# dc_motor_driver_v10.net
KiCad netlist of a schematic drawn in EAGLE
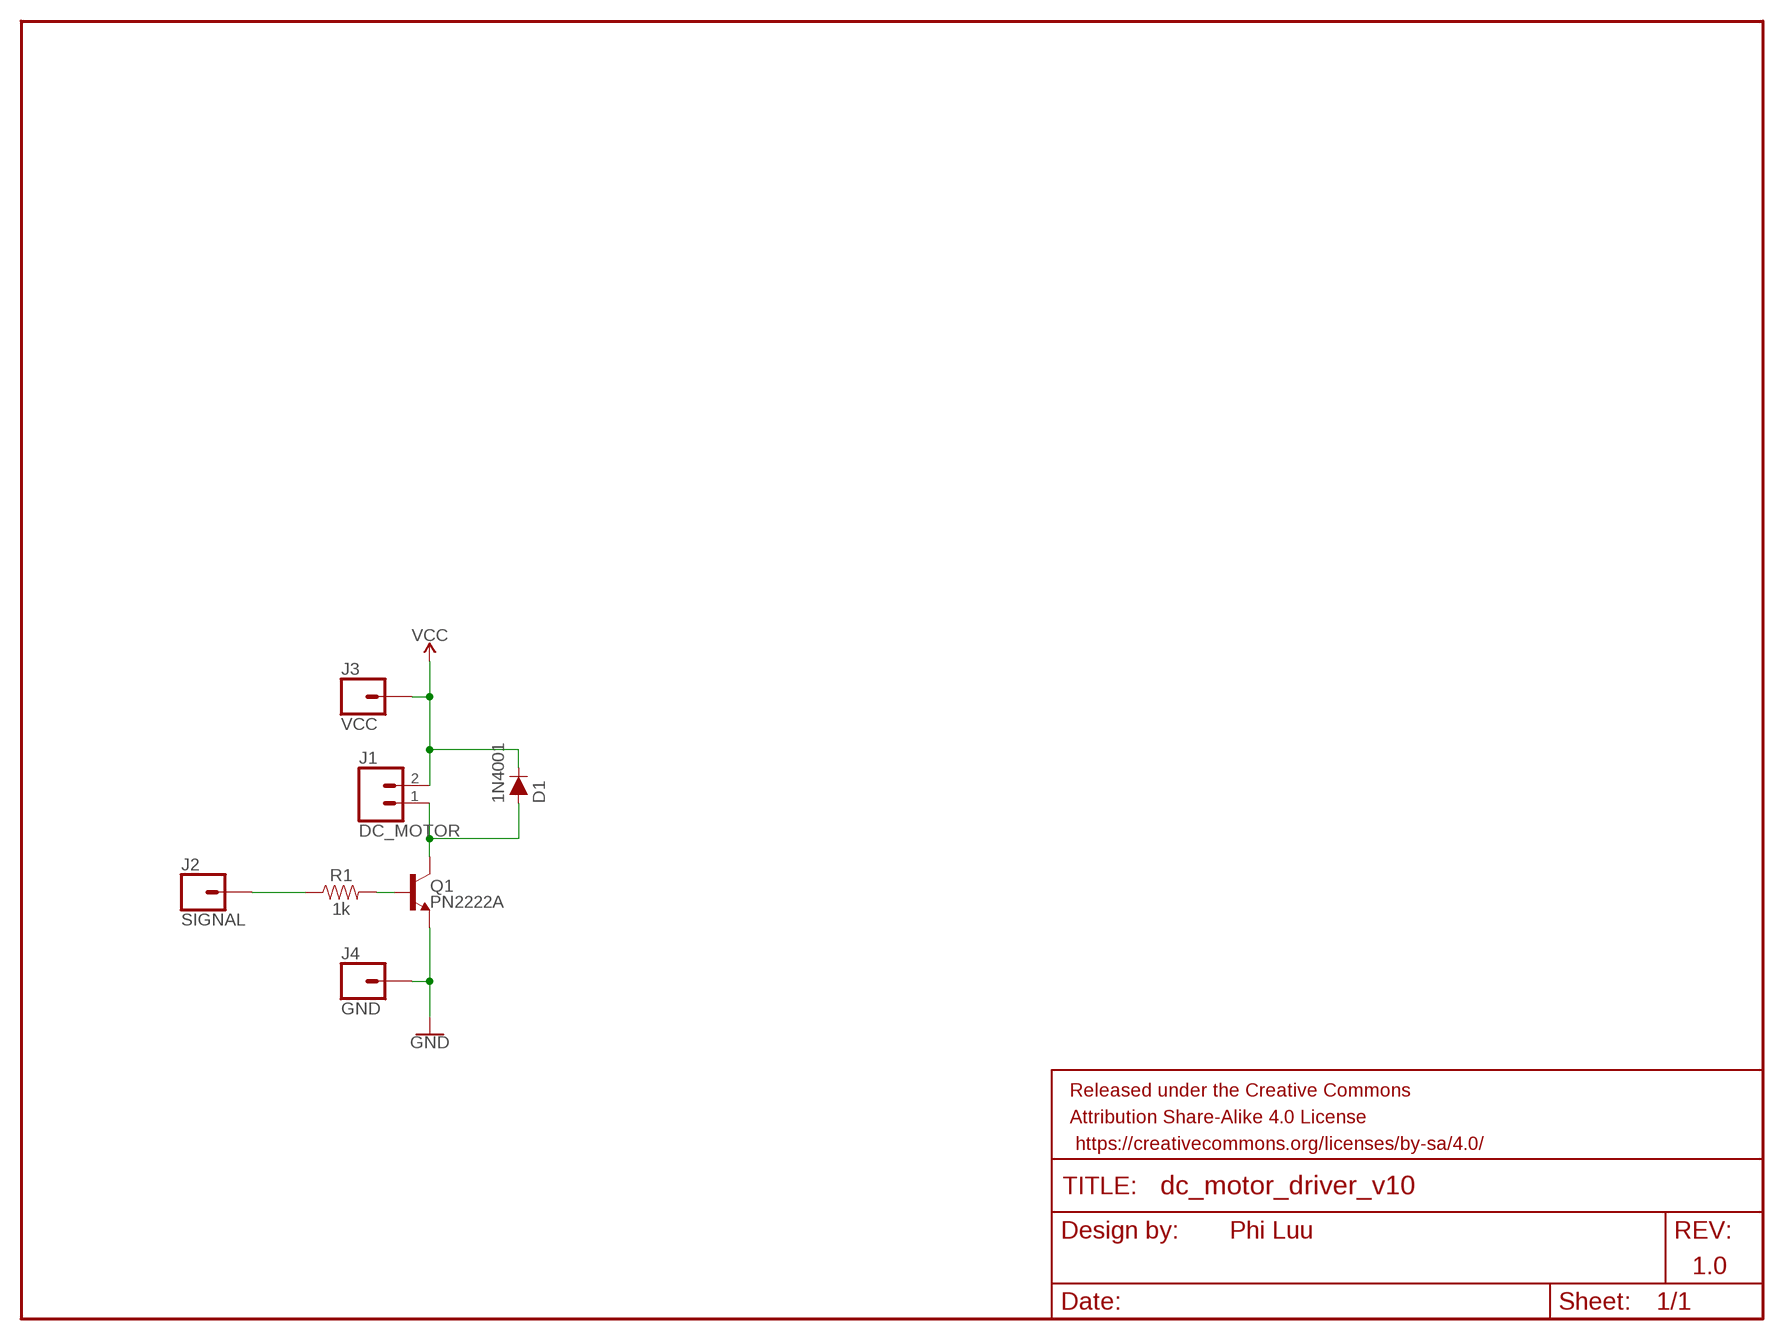
[diagram p0: schematic, sheet 1]

(export (version "E")
  (design (tool "Eeschema 10.0.6"))
  (components
    (comp (ref "D1")
      (value "1N4001")
      (footprint "eagle-import:DIODE-1N4001")
      (libsource (lib "eagle-import") (part "DIODE-PTH"))
    )
    (comp (ref "FRAME1")
      (value "FRAME-LETTER")
      (footprint "eagle-import:CREATIVE_COMMONS")
      (libsource (lib "eagle-import") (part "FRAME-LETTER"))
    )
    (comp (ref "J1")
      (value "DC_MOTOR")
      (footprint "eagle-import:1X02")
      (libsource (lib "eagle-import") (part "CONN_02"))
    )
    (comp (ref "J2")
      (value "SIGNAL")
      (footprint "eagle-import:1X01")
      (libsource (lib "eagle-import") (part "CONN_01"))
    )
    (comp (ref "J3")
      (value "VCC")
      (footprint "eagle-import:1X01")
      (libsource (lib "eagle-import") (part "CONN_01"))
    )
    (comp (ref "J4")
      (value "GND")
      (footprint "eagle-import:1X01")
      (libsource (lib "eagle-import") (part "CONN_01"))
    )
    (comp (ref "Q1")
      (value "PN2222A")
      (footprint "eagle-import:TO-92")
      (libsource (lib "eagle-import") (part "TRANS_NPN-P2N2222A"))
    )
    (comp (ref "R1")
      (value "1k")
      (footprint "eagle-import:AXIAL-0.3")
      (libsource (lib "eagle-import") (part "1KOHM-HORIZ-1/4W-5%"))
    )
  )
  (nets
    (net (code "1") (name "GND") (class "Default")
      (node (ref "J4") (pin "1") (pinfunction "1_1") (pintype "passive"))
      (node (ref "Q1") (pin "3") (pinfunction "E_3") (pintype "passive"))
    )
    (net (code "2") (name "Net-(Q1-B)") (class "Default")
      (node (ref "Q1") (pin "2") (pinfunction "B_2") (pintype "passive"))
      (node (ref "R1") (pin "P$2") (pinfunction "2_P$2") (pintype "passive"))
    )
    (net (code "3") (name "Net-(Q1-C)") (class "Default")
      (node (ref "D1") (pin "A") (pinfunction "A_A") (pintype "passive"))
      (node (ref "J1") (pin "1") (pinfunction "1_1") (pintype "passive"))
      (node (ref "Q1") (pin "1") (pinfunction "C_1") (pintype "passive"))
    )
    (net (code "4") (name "Net-(R1-1)") (class "Default")
      (node (ref "J2") (pin "1") (pinfunction "1_1") (pintype "passive"))
      (node (ref "R1") (pin "P$1") (pinfunction "1_P$1") (pintype "passive"))
    )
    (net (code "5") (name "VCC") (class "Default")
      (node (ref "D1") (pin "C") (pinfunction "C_C") (pintype "passive"))
      (node (ref "J1") (pin "2") (pinfunction "2_2") (pintype "passive"))
      (node (ref "J3") (pin "1") (pinfunction "1_1") (pintype "passive"))
    )
  )
)
